# HeadsetR4.net
KiCad netlist of a schematic drawn in EAGLE
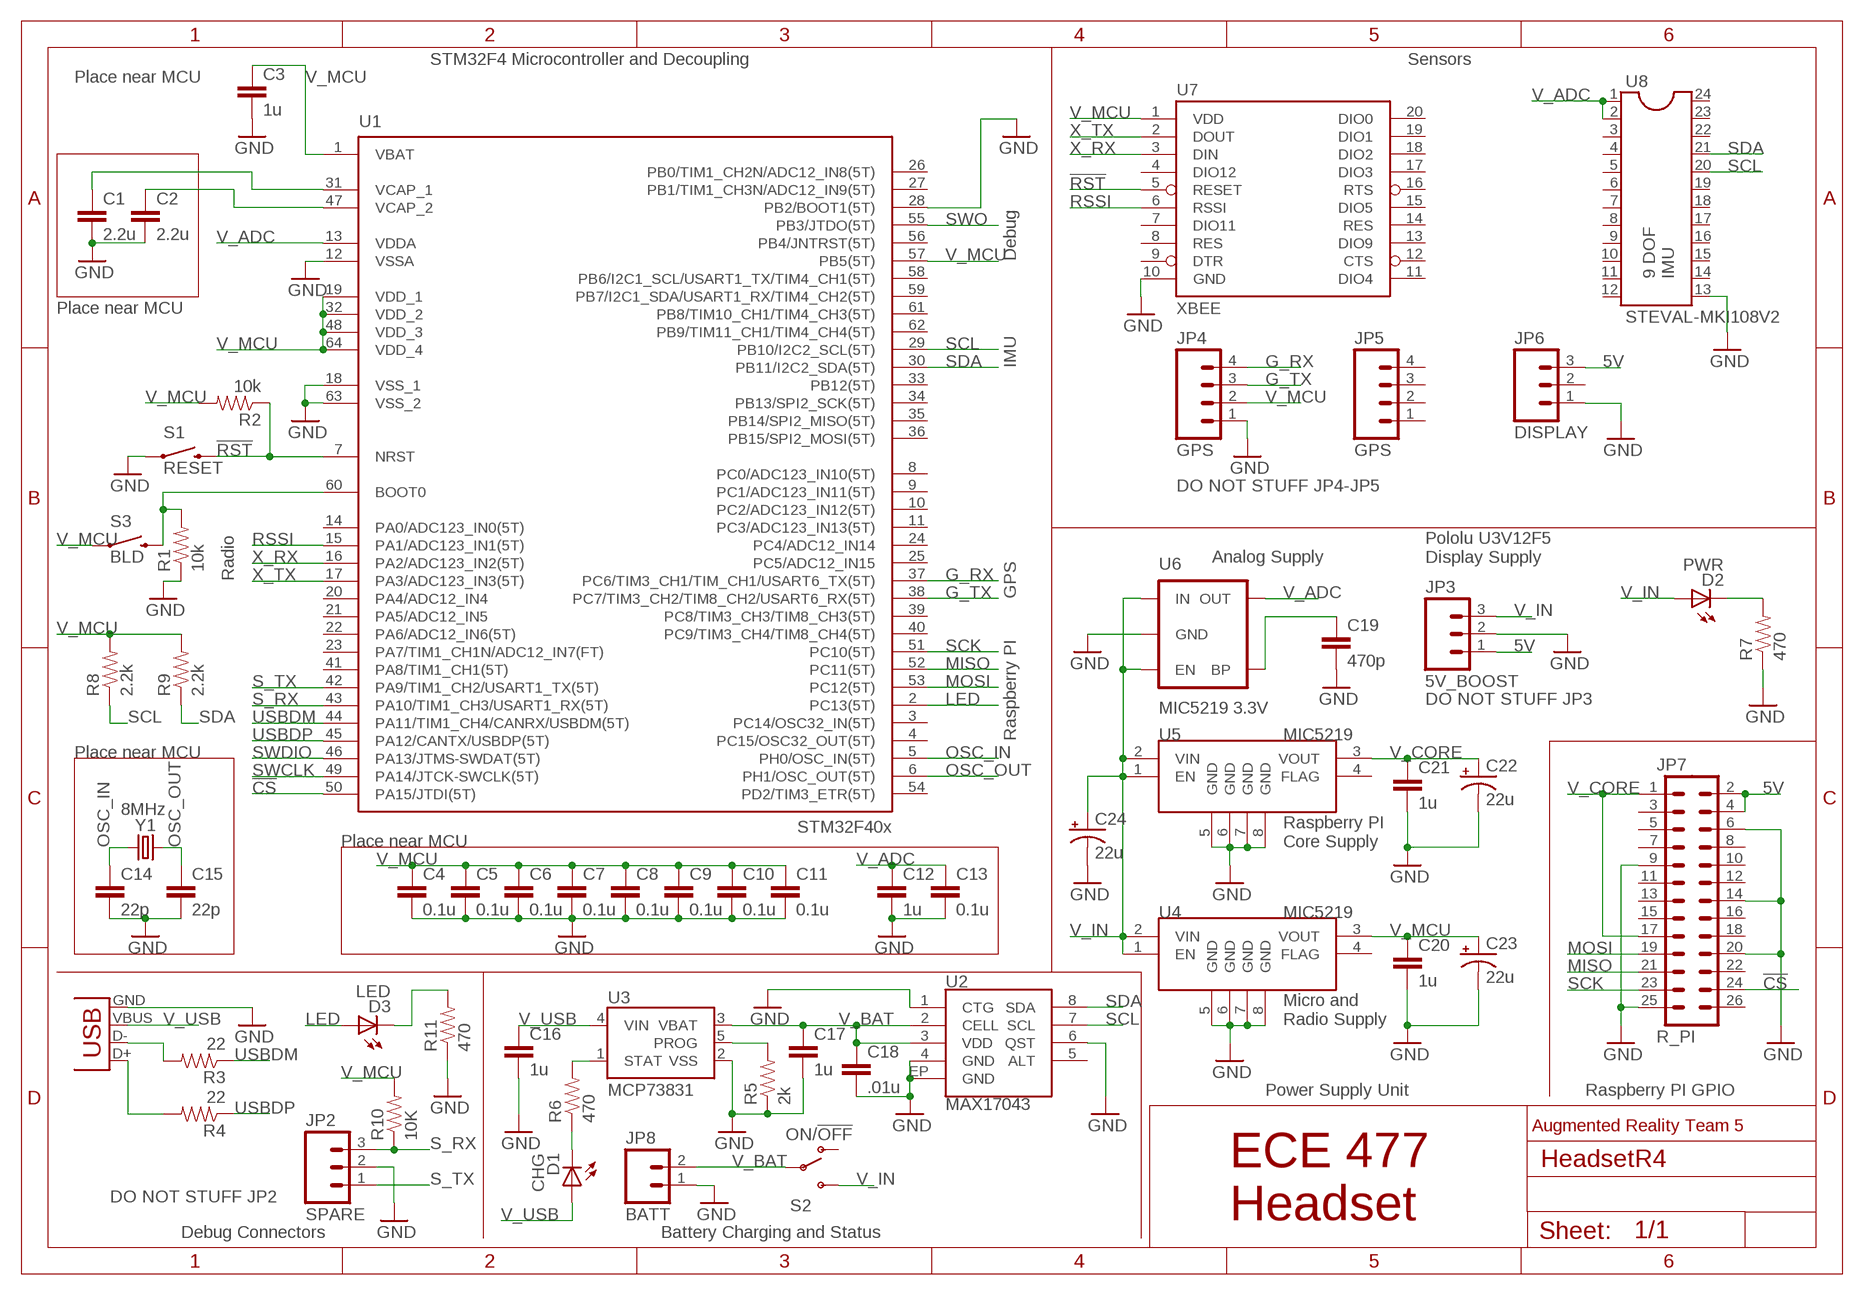
[diagram p0: schematic, sheet 1]

(export (version "E")
  (design (tool "Eeschema 10.0.6"))
  (components
    (comp (ref "C1")
      (value "2.2u")
      (footprint "eagle-import:1206")
      (libsource (lib "eagle-import") (part "CAP1206"))
    )
    (comp (ref "C2")
      (value "2.2u")
      (footprint "eagle-import:1206")
      (libsource (lib "eagle-import") (part "CAP1206"))
    )
    (comp (ref "C3")
      (value "1u")
      (footprint "eagle-import:1206")
      (libsource (lib "eagle-import") (part "CAP1206"))
    )
    (comp (ref "C4")
      (value "0.1u")
      (footprint "eagle-import:1206")
      (libsource (lib "eagle-import") (part "CAP1206"))
    )
    (comp (ref "C5")
      (value "0.1u")
      (footprint "eagle-import:1206")
      (libsource (lib "eagle-import") (part "CAP1206"))
    )
    (comp (ref "C6")
      (value "0.1u")
      (footprint "eagle-import:1206")
      (libsource (lib "eagle-import") (part "CAP1206"))
    )
    (comp (ref "C7")
      (value "0.1u")
      (footprint "eagle-import:1206")
      (libsource (lib "eagle-import") (part "CAP1206"))
    )
    (comp (ref "C8")
      (value "0.1u")
      (footprint "eagle-import:1206")
      (libsource (lib "eagle-import") (part "CAP1206"))
    )
    (comp (ref "C9")
      (value "0.1u")
      (footprint "eagle-import:1206")
      (libsource (lib "eagle-import") (part "CAP1206"))
    )
    (comp (ref "C10")
      (value "0.1u")
      (footprint "eagle-import:1206")
      (libsource (lib "eagle-import") (part "CAP1206"))
    )
    (comp (ref "C11")
      (value "0.1u")
      (footprint "eagle-import:1206")
      (libsource (lib "eagle-import") (part "CAP1206"))
    )
    (comp (ref "C12")
      (value "1u")
      (footprint "eagle-import:1206")
      (libsource (lib "eagle-import") (part "CAP1206"))
    )
    (comp (ref "C13")
      (value "0.1u")
      (footprint "eagle-import:1206")
      (libsource (lib "eagle-import") (part "CAP1206"))
    )
    (comp (ref "C14")
      (value "22p")
      (footprint "eagle-import:1206")
      (libsource (lib "eagle-import") (part "CAP1206"))
    )
    (comp (ref "C15")
      (value "22p")
      (footprint "eagle-import:1206")
      (libsource (lib "eagle-import") (part "CAP1206"))
    )
    (comp (ref "C16")
      (value "1u")
      (footprint "eagle-import:1206")
      (libsource (lib "eagle-import") (part "CAP1206"))
    )
    (comp (ref "C17")
      (value "1u")
      (footprint "eagle-import:1206")
      (libsource (lib "eagle-import") (part "CAP1206"))
    )
    (comp (ref "C18")
      (value ".01u")
      (footprint "eagle-import:1206")
      (libsource (lib "eagle-import") (part "CAP1206"))
    )
    (comp (ref "C19")
      (value "470p")
      (footprint "eagle-import:1206")
      (libsource (lib "eagle-import") (part "CAP1206"))
    )
    (comp (ref "C20")
      (value "1u")
      (footprint "eagle-import:1206")
      (libsource (lib "eagle-import") (part "CAP1206"))
    )
    (comp (ref "C21")
      (value "1u")
      (footprint "eagle-import:1206")
      (libsource (lib "eagle-import") (part "CAP1206"))
    )
    (comp (ref "C22")
      (value "22u")
      (footprint "eagle-import:PANASONIC_D")
      (libsource (lib "eagle-import") (part "CAP_POLD"))
    )
    (comp (ref "C23")
      (value "22u")
      (footprint "eagle-import:PANASONIC_D")
      (libsource (lib "eagle-import") (part "CAP_POLD"))
    )
    (comp (ref "C24")
      (value "22u")
      (footprint "eagle-import:PANASONIC_D")
      (libsource (lib "eagle-import") (part "CAP_POLD"))
    )
    (comp (ref "D1")
      (value "CHG")
      (footprint "eagle-import:LED-1206")
      (libsource (lib "eagle-import") (part "LED-RED1206"))
    )
    (comp (ref "D2")
      (value "PWR")
      (footprint "eagle-import:LED-1206")
      (libsource (lib "eagle-import") (part "LED-RED1206"))
    )
    (comp (ref "D3")
      (value "LED")
      (footprint "eagle-import:LED-1206")
      (libsource (lib "eagle-import") (part "LED-RED1206"))
    )
    (comp (ref "JP1")
      (value "USBSMD")
      (footprint "eagle-import:USB-MINIB")
      (libsource (lib "eagle-import") (part "USBSMD"))
    )
    (comp (ref "JP2")
      (value "SPARE")
      (footprint "eagle-import:1X03")
      (libsource (lib "eagle-import") (part "M03PTH"))
    )
    (comp (ref "JP3")
      (value "5V_BOOST")
      (footprint "eagle-import:1X03")
      (libsource (lib "eagle-import") (part "M03PTH"))
    )
    (comp (ref "JP4")
      (value "GPS")
      (footprint "eagle-import:1X04")
      (libsource (lib "eagle-import") (part "M04PTH"))
    )
    (comp (ref "JP5")
      (value "GPS")
      (footprint "eagle-import:1X04")
      (libsource (lib "eagle-import") (part "M04PTH"))
    )
    (comp (ref "JP6")
      (value "DISPLAY")
      (footprint "eagle-import:1X03")
      (libsource (lib "eagle-import") (part "M03PTH"))
    )
    (comp (ref "JP7")
      (value "R_PI")
      (footprint "eagle-import:2X13")
      (libsource (lib "eagle-import") (part "M13X22X13"))
    )
    (comp (ref "JP8")
      (value "BATT")
      (footprint "eagle-import:JST-2-PTH")
      (libsource (lib "eagle-import") (part "M02JST-PTH-2"))
    )
    (comp (ref "R1")
      (value "10k")
      (footprint "eagle-import:1206")
      (libsource (lib "eagle-import") (part "RES1206"))
    )
    (comp (ref "R2")
      (value "10k")
      (footprint "eagle-import:1206")
      (libsource (lib "eagle-import") (part "RES1206"))
    )
    (comp (ref "R3")
      (value "22")
      (footprint "eagle-import:1206")
      (libsource (lib "eagle-import") (part "RES1206"))
    )
    (comp (ref "R4")
      (value "22")
      (footprint "eagle-import:1206")
      (libsource (lib "eagle-import") (part "RES1206"))
    )
    (comp (ref "R5")
      (value "2k")
      (footprint "eagle-import:1206")
      (libsource (lib "eagle-import") (part "RES1206"))
    )
    (comp (ref "R6")
      (value "470")
      (footprint "eagle-import:1206")
      (libsource (lib "eagle-import") (part "RES1206"))
    )
    (comp (ref "R7")
      (value "470")
      (footprint "eagle-import:1206")
      (libsource (lib "eagle-import") (part "RES1206"))
    )
    (comp (ref "R8")
      (value "2.2k")
      (footprint "eagle-import:1206")
      (libsource (lib "eagle-import") (part "RES1206"))
    )
    (comp (ref "R9")
      (value "2.2k")
      (footprint "eagle-import:1206")
      (libsource (lib "eagle-import") (part "RES1206"))
    )
    (comp (ref "R10")
      (value "10K")
      (footprint "eagle-import:1206")
      (libsource (lib "eagle-import") (part "RES1206"))
    )
    (comp (ref "R11")
      (value "470")
      (footprint "eagle-import:1206")
      (libsource (lib "eagle-import") (part "RES1206"))
    )
    (comp (ref "S1")
      (value "RESET")
      (footprint "eagle-import:TACTILE-PTH")
      (libsource (lib "eagle-import") (part "SWITCH-MOMENTARY-2PTH"))
    )
    (comp (ref "S2")
      (value "ON/!OFF!")
      (footprint "eagle-import:SWITCH-SPDT")
      (libsource (lib "eagle-import") (part "SWITCH-SPDTPTH"))
    )
    (comp (ref "S3")
      (value "BLD")
      (footprint "eagle-import:TACTILE-PTH")
      (libsource (lib "eagle-import") (part "SWITCH-MOMENTARY-2PTH"))
    )
    (comp (ref "U1")
      (value "STM32F405RGT6")
      (footprint "eagle-import:TQFP64")
      (libsource (lib "eagle-import") (part "STM32F405R"))
    )
    (comp (ref "U2")
      (value "MAX17043")
      (footprint "eagle-import:TDFN-8")
      (libsource (lib "eagle-import") (part "MAX1704X"))
    )
    (comp (ref "U3")
      (value "MCP73831")
      (footprint "eagle-import:SOT23-5")
      (libsource (lib "eagle-import") (part "MCP73831"))
    )
    (comp (ref "U4")
      (value "MIC5219")
      (footprint "eagle-import:MSOP8")
      (libsource (lib "eagle-import") (part "V_REG_MIC5216"))
    )
    (comp (ref "U5")
      (value "MIC5219")
      (footprint "eagle-import:MSOP8")
      (libsource (lib "eagle-import") (part "V_REG_MIC5216"))
    )
    (comp (ref "U6")
      (value "MIC5219 3.3V")
      (footprint "eagle-import:SOT23-5")
      (libsource (lib "eagle-import") (part "V_REG_MIC52193.3V"))
    )
    (comp (ref "U7")
      (value "XBEE")
      (footprint "eagle-import:XBEE-1")
      (libsource (lib "eagle-import") (part "XBEE-1B1"))
    )
    (comp (ref "U8")
      (value "STEVAL-MKI108V2")
      (footprint "eagle-import:DIL24-6")
      (libsource (lib "eagle-import") (part "DIL24-6"))
    )
    (comp (ref "Y1")
      (value "8MHz")
      (footprint "eagle-import:HC49US")
      (libsource (lib "eagle-import") (part "CRYSTALHC49US"))
    )
  )
  (nets
    (net (code "1") (name "/5V") (class "Default")
      (node (ref "JP3") (pin "1") (pinfunction "1_1") (pintype "passive"))
      (node (ref "JP6") (pin "3") (pinfunction "3_3") (pintype "passive"))
      (node (ref "JP7") (pin "2") (pinfunction "2_2") (pintype "passive"))
      (node (ref "JP7") (pin "4") (pinfunction "4_4") (pintype "passive"))
    )
    (net (code "2") (name "/G_RX") (class "Default")
      (node (ref "JP4") (pin "4") (pinfunction "4_4") (pintype "passive"))
      (node (ref "U1") (pin "37") (pinfunction "PC6/TIM3_CH1/TIM_CH1/USART6_TX(5T)_37") (pintype "bidirectional"))
    )
    (net (code "3") (name "/G_TX") (class "Default")
      (node (ref "JP4") (pin "3") (pinfunction "3_3") (pintype "passive"))
      (node (ref "U1") (pin "38") (pinfunction "PC7/TIM3_CH2/TIM8_CH2/USART6_RX(5T)_38") (pintype "bidirectional"))
    )
    (net (code "4") (name "/LED") (class "Default")
      (node (ref "D3") (pin "A") (pinfunction "A_A") (pintype "passive"))
      (node (ref "U1") (pin "2") (pinfunction "PC13(5T)_2") (pintype "bidirectional"))
    )
    (net (code "5") (name "/MISO") (class "Default")
      (node (ref "JP7") (pin "21") (pinfunction "21_21") (pintype "passive"))
      (node (ref "U1") (pin "52") (pinfunction "PC11(5T)_52") (pintype "bidirectional"))
    )
    (net (code "6") (name "/MOSI") (class "Default")
      (node (ref "JP7") (pin "19") (pinfunction "19_19") (pintype "passive"))
      (node (ref "U1") (pin "53") (pinfunction "PC12(5T)_53") (pintype "bidirectional"))
    )
    (net (code "7") (name "/OSC_IN") (class "Default")
      (node (ref "C14") (pin "1") (pinfunction "1_1") (pintype "passive"))
      (node (ref "U1") (pin "5") (pinfunction "PH0/OSC_IN(5T)_5") (pintype "bidirectional"))
      (node (ref "Y1") (pin "1") (pinfunction "1_1") (pintype "passive"))
    )
    (net (code "8") (name "/OSC_OUT") (class "Default")
      (node (ref "C15") (pin "1") (pinfunction "1_1") (pintype "passive"))
      (node (ref "U1") (pin "6") (pinfunction "PH1/OSC_OUT(5T)_6") (pintype "bidirectional"))
      (node (ref "Y1") (pin "2") (pinfunction "2_2") (pintype "passive"))
    )
    (net (code "9") (name "/RSSI") (class "Default")
      (node (ref "U1") (pin "15") (pinfunction "PA1/ADC123_IN1(5T)_15") (pintype "bidirectional"))
      (node (ref "U7") (pin "6") (pinfunction "RSSI_6") (pintype "bidirectional"))
    )
    (net (code "10") (name "/SCK") (class "Default")
      (node (ref "JP7") (pin "23") (pinfunction "23_23") (pintype "passive"))
      (node (ref "U1") (pin "51") (pinfunction "PC10(5T)_51") (pintype "bidirectional"))
    )
    (net (code "11") (name "/SCL") (class "Default")
      (node (ref "R8") (pin "1") (pinfunction "1_1") (pintype "passive"))
      (node (ref "U1") (pin "29") (pinfunction "PB10/I2C2_SCL(5T)_29") (pintype "bidirectional"))
      (node (ref "U2") (pin "7") (pinfunction "SCL_7") (pintype "bidirectional"))
      (node (ref "U8") (pin "20") (pinfunction "20_20") (pintype "passive"))
    )
    (net (code "12") (name "/SDA") (class "Default")
      (node (ref "R9") (pin "1") (pinfunction "1_1") (pintype "passive"))
      (node (ref "U1") (pin "30") (pinfunction "PB11/I2C2_SDA(5T)_30") (pintype "bidirectional"))
      (node (ref "U2") (pin "8") (pinfunction "SDA_8") (pintype "bidirectional"))
      (node (ref "U8") (pin "21") (pinfunction "21_21") (pintype "passive"))
    )
    (net (code "13") (name "/SWCLK") (class "Default")
      (node (ref "U1") (pin "49") (pinfunction "PA14/JTCK-SWCLK(5T)_49") (pintype "bidirectional"))
    )
    (net (code "14") (name "/SWDIO") (class "Default")
      (node (ref "U1") (pin "46") (pinfunction "PA13/JTMS-SWDAT(5T)_46") (pintype "bidirectional"))
    )
    (net (code "15") (name "/SWO") (class "Default")
      (node (ref "U1") (pin "55") (pinfunction "PB3/JTDO(5T)_55") (pintype "bidirectional"))
    )
    (net (code "16") (name "/S_RX") (class "Default")
      (node (ref "JP2") (pin "3") (pinfunction "3_3") (pintype "passive"))
      (node (ref "R10") (pin "1") (pinfunction "1_1") (pintype "passive"))
      (node (ref "U1") (pin "43") (pinfunction "PA10/TIM1_CH3/USART1_RX(5T)_43") (pintype "bidirectional"))
    )
    (net (code "17") (name "/S_TX") (class "Default")
      (node (ref "JP2") (pin "1") (pinfunction "1_1") (pintype "passive"))
      (node (ref "U1") (pin "42") (pinfunction "PA9/TIM1_CH2/USART1_TX(5T)_42") (pintype "bidirectional"))
    )
    (net (code "18") (name "/USBDM") (class "Default")
      (node (ref "R3") (pin "1") (pinfunction "1_1") (pintype "passive"))
      (node (ref "U1") (pin "44") (pinfunction "PA11/TIM1_CH4/CANRX/USBDM(5T)_44") (pintype "bidirectional"))
    )
    (net (code "19") (name "/USBDP") (class "Default")
      (node (ref "R4") (pin "1") (pinfunction "1_1") (pintype "passive"))
      (node (ref "U1") (pin "45") (pinfunction "PA12/CANTX/USBDP(5T)_45") (pintype "bidirectional"))
    )
    (net (code "20") (name "/V_ADC") (class "Default")
      (node (ref "C12") (pin "1") (pinfunction "1_1") (pintype "passive"))
      (node (ref "C13") (pin "1") (pinfunction "1_1") (pintype "passive"))
      (node (ref "U1") (pin "13") (pinfunction "VDDA_13") (pintype "bidirectional"))
      (node (ref "U6") (pin "5") (pinfunction "OUT_5") (pintype "passive"))
      (node (ref "U8") (pin "1") (pinfunction "1_1") (pintype "passive"))
      (node (ref "U8") (pin "2") (pinfunction "2_2") (pintype "passive"))
    )
    (net (code "21") (name "/V_BAT") (class "Default")
      (node (ref "C17") (pin "1") (pinfunction "1_1") (pintype "passive"))
      (node (ref "C18") (pin "1") (pinfunction "1_1") (pintype "passive"))
      (node (ref "JP8") (pin "2") (pinfunction "2_2") (pintype "passive"))
      (node (ref "S2") (pin "2") (pinfunction "P_2") (pintype "passive"))
      (node (ref "U2") (pin "2") (pinfunction "CELL_2") (pintype "bidirectional"))
      (node (ref "U2") (pin "3") (pinfunction "VDD_3") (pintype "bidirectional"))
      (node (ref "U3") (pin "3") (pinfunction "VBAT_3") (pintype "power_in"))
    )
    (net (code "22") (name "/V_CORE") (class "Default")
      (node (ref "C21") (pin "1") (pinfunction "1_1") (pintype "passive"))
      (node (ref "C22") (pin "+") (pinfunction "+_+") (pintype "passive"))
      (node (ref "JP7") (pin "1") (pinfunction "1_1") (pintype "passive"))
      (node (ref "JP7") (pin "17") (pinfunction "17_17") (pintype "passive"))
      (node (ref "U5") (pin "3") (pinfunction "VOUT_3") (pintype "bidirectional"))
    )
    (net (code "23") (name "/V_IN") (class "Default")
      (node (ref "C24") (pin "+") (pinfunction "+_+") (pintype "passive"))
      (node (ref "D2") (pin "A") (pinfunction "A_A") (pintype "passive"))
      (node (ref "JP3") (pin "3") (pinfunction "3_3") (pintype "passive"))
      (node (ref "S2") (pin "3") (pinfunction "S_3") (pintype "passive"))
      (node (ref "U4") (pin "1") (pinfunction "EN_1") (pintype "bidirectional"))
      (node (ref "U4") (pin "2") (pinfunction "VIN_2") (pintype "bidirectional"))
      (node (ref "U5") (pin "1") (pinfunction "EN_1") (pintype "bidirectional"))
      (node (ref "U5") (pin "2") (pinfunction "VIN_2") (pintype "bidirectional"))
      (node (ref "U6") (pin "1") (pinfunction "IN_1") (pintype "input"))
      (node (ref "U6") (pin "3") (pinfunction "EN_3") (pintype "input"))
    )
    (net (code "24") (name "/V_MCU") (class "Default")
      (node (ref "C10") (pin "1") (pinfunction "1_1") (pintype "passive"))
      (node (ref "C11") (pin "1") (pinfunction "1_1") (pintype "passive"))
      (node (ref "C20") (pin "1") (pinfunction "1_1") (pintype "passive"))
      (node (ref "C23") (pin "+") (pinfunction "+_+") (pintype "passive"))
      (node (ref "C3") (pin "1") (pinfunction "1_1") (pintype "passive"))
      (node (ref "C4") (pin "1") (pinfunction "1_1") (pintype "passive"))
      (node (ref "C5") (pin "1") (pinfunction "1_1") (pintype "passive"))
      (node (ref "C6") (pin "1") (pinfunction "1_1") (pintype "passive"))
      (node (ref "C7") (pin "1") (pinfunction "1_1") (pintype "passive"))
      (node (ref "C8") (pin "1") (pinfunction "1_1") (pintype "passive"))
      (node (ref "C9") (pin "1") (pinfunction "1_1") (pintype "passive"))
      (node (ref "JP4") (pin "2") (pinfunction "2_2") (pintype "passive"))
      (node (ref "R10") (pin "2") (pinfunction "2_2") (pintype "passive"))
      (node (ref "R2") (pin "2") (pinfunction "2_2") (pintype "passive"))
      (node (ref "R8") (pin "2") (pinfunction "2_2") (pintype "passive"))
      (node (ref "R9") (pin "2") (pinfunction "2_2") (pintype "passive"))
      (node (ref "S3") (pin "1") (pinfunction "1_1") (pintype "passive"))
      (node (ref "U1") (pin "1") (pinfunction "VBAT_1") (pintype "bidirectional"))
      (node (ref "U1") (pin "19") (pinfunction "VDD_1_19") (pintype "bidirectional"))
      (node (ref "U1") (pin "32") (pinfunction "VDD_2_32") (pintype "bidirectional"))
      (node (ref "U1") (pin "48") (pinfunction "VDD_3_48") (pintype "bidirectional"))
      (node (ref "U1") (pin "57") (pinfunction "PB5(5T)_57") (pintype "bidirectional"))
      (node (ref "U1") (pin "64") (pinfunction "VDD_4_64") (pintype "bidirectional"))
      (node (ref "U4") (pin "3") (pinfunction "VOUT_3") (pintype "bidirectional"))
      (node (ref "U7") (pin "1") (pinfunction "VDD_1") (pintype "power_in"))
    )
    (net (code "25") (name "/V_USB") (class "Default")
      (node (ref "C16") (pin "1") (pinfunction "1_1") (pintype "passive"))
      (node (ref "D1") (pin "A") (pinfunction "A_A") (pintype "passive"))
      (node (ref "JP1") (pin "VBUS") (pinfunction "VBUS_VBUS") (pintype "bidirectional"))
      (node (ref "U3") (pin "4") (pinfunction "VIN_4") (pintype "power_in"))
    )
    (net (code "26") (name "/X_RX") (class "Default")
      (node (ref "U1") (pin "16") (pinfunction "PA2/ADC123_IN2(5T)_16") (pintype "bidirectional"))
      (node (ref "U7") (pin "3") (pinfunction "DIN_3") (pintype "input"))
    )
    (net (code "27") (name "/X_TX") (class "Default")
      (node (ref "U1") (pin "17") (pinfunction "PA3/ADC123_IN3(5T)_17") (pintype "bidirectional"))
      (node (ref "U7") (pin "2") (pinfunction "DOUT_2") (pintype "output"))
    )
    (net (code "28") (name "/~{CS}") (class "Default")
      (node (ref "JP7") (pin "24") (pinfunction "24_24") (pintype "passive"))
      (node (ref "U1") (pin "50") (pinfunction "PA15/JTDI(5T)_50") (pintype "bidirectional"))
    )
    (net (code "29") (name "/~{RST}") (class "Default")
      (node (ref "R2") (pin "1") (pinfunction "1_1") (pintype "passive"))
      (node (ref "S1") (pin "3") (pinfunction "2_3") (pintype "passive"))
      (node (ref "U1") (pin "7") (pinfunction "NRST_7") (pintype "bidirectional"))
      (node (ref "U7") (pin "5") (pinfunction "RESET_5") (pintype "input"))
    )
    (net (code "30") (name "GND") (class "Default")
      (node (ref "C1") (pin "2") (pinfunction "2_2") (pintype "passive"))
      (node (ref "C10") (pin "2") (pinfunction "2_2") (pintype "passive"))
      (node (ref "C11") (pin "2") (pinfunction "2_2") (pintype "passive"))
      (node (ref "C12") (pin "2") (pinfunction "2_2") (pintype "passive"))
      (node (ref "C13") (pin "2") (pinfunction "2_2") (pintype "passive"))
      (node (ref "C14") (pin "2") (pinfunction "2_2") (pintype "passive"))
      (node (ref "C15") (pin "2") (pinfunction "2_2") (pintype "passive"))
      (node (ref "C16") (pin "2") (pinfunction "2_2") (pintype "passive"))
      (node (ref "C17") (pin "2") (pinfunction "2_2") (pintype "passive"))
      (node (ref "C18") (pin "2") (pinfunction "2_2") (pintype "passive"))
      (node (ref "C19") (pin "2") (pinfunction "2_2") (pintype "passive"))
      (node (ref "C2") (pin "2") (pinfunction "2_2") (pintype "passive"))
      (node (ref "C20") (pin "2") (pinfunction "2_2") (pintype "passive"))
      (node (ref "C21") (pin "2") (pinfunction "2_2") (pintype "passive"))
      (node (ref "C22") (pin "-") (pinfunction "-_-") (pintype "passive"))
      (node (ref "C23") (pin "-") (pinfunction "-_-") (pintype "passive"))
      (node (ref "C24") (pin "-") (pinfunction "-_-") (pintype "passive"))
      (node (ref "C3") (pin "2") (pinfunction "2_2") (pintype "passive"))
      (node (ref "C4") (pin "2") (pinfunction "2_2") (pintype "passive"))
      (node (ref "C5") (pin "2") (pinfunction "2_2") (pintype "passive"))
      (node (ref "C6") (pin "2") (pinfunction "2_2") (pintype "passive"))
      (node (ref "C7") (pin "2") (pinfunction "2_2") (pintype "passive"))
      (node (ref "C8") (pin "2") (pinfunction "2_2") (pintype "passive"))
      (node (ref "C9") (pin "2") (pinfunction "2_2") (pintype "passive"))
      (node (ref "JP1") (pin "GND") (pinfunction "GND_GND") (pintype "bidirectional"))
      (node (ref "JP2") (pin "2") (pinfunction "2_2") (pintype "passive"))
      (node (ref "JP3") (pin "2") (pinfunction "2_2") (pintype "passive"))
      (node (ref "JP4") (pin "1") (pinfunction "1_1") (pintype "passive"))
      (node (ref "JP6") (pin "1") (pinfunction "1_1") (pintype "passive"))
      (node (ref "JP7") (pin "14") (pinfunction "14_14") (pintype "passive"))
      (node (ref "JP7") (pin "20") (pinfunction "20_20") (pintype "passive"))
      (node (ref "JP7") (pin "25") (pinfunction "25_25") (pintype "passive"))
      (node (ref "JP7") (pin "6") (pinfunction "6_6") (pintype "passive"))
      (node (ref "JP7") (pin "9") (pinfunction "9_9") (pintype "passive"))
      (node (ref "JP8") (pin "1") (pinfunction "1_1") (pintype "passive"))
      (node (ref "R1") (pin "1") (pinfunction "1_1") (pintype "passive"))
      (node (ref "R11") (pin "1") (pinfunction "1_1") (pintype "passive"))
      (node (ref "R5") (pin "1") (pinfunction "1_1") (pintype "passive"))
      (node (ref "R7") (pin "1") (pinfunction "1_1") (pintype "passive"))
      (node (ref "S1") (pin "1") (pinfunction "1_1") (pintype "passive"))
      (node (ref "U1") (pin "12") (pinfunction "VSSA_12") (pintype "bidirectional"))
      (node (ref "U1") (pin "18") (pinfunction "VSS_1_18") (pintype "bidirectional"))
      (node (ref "U1") (pin "28") (pinfunction "PB2/BOOT1(5T)_28") (pintype "bidirectional"))
      (node (ref "U1") (pin "63") (pinfunction "VSS_2_63") (pintype "bidirectional"))
      (node (ref "U2") (pin "1") (pinfunction "CTG_1") (pintype "bidirectional"))
      (node (ref "U2") (pin "4") (pinfunction "GND_4") (pintype "bidirectional"))
      (node (ref "U2") (pin "6") (pinfunction "QST_6") (pintype "bidirectional"))
      (node (ref "U2") (pin "EP") (pinfunction "GND_EP") (pintype "bidirectional"))
      (node (ref "U3") (pin "2") (pinfunction "VSS_2") (pintype "power_in"))
      (node (ref "U4") (pin "5") (pinfunction "GND_5") (pintype "bidirectional"))
      (node (ref "U4") (pin "6") (pinfunction "GND_6") (pintype "bidirectional"))
      (node (ref "U4") (pin "7") (pinfunction "GND_7") (pintype "bidirectional"))
      (node (ref "U4") (pin "8") (pinfunction "GND_8") (pintype "bidirectional"))
      (node (ref "U5") (pin "5") (pinfunction "GND_5") (pintype "bidirectional"))
      (node (ref "U5") (pin "6") (pinfunction "GND_6") (pintype "bidirectional"))
      (node (ref "U5") (pin "7") (pinfunction "GND_7") (pintype "bidirectional"))
      (node (ref "U5") (pin "8") (pinfunction "GND_8") (pintype "bidirectional"))
      (node (ref "U6") (pin "2") (pinfunction "GND_2") (pintype "input"))
      (node (ref "U7") (pin "10") (pinfunction "GND_10") (pintype "power_in"))
      (node (ref "U8") (pin "13") (pinfunction "13_13") (pintype "passive"))
    )
    (net (code "31") (name "Net-(D1-PadC)") (class "Default")
      (node (ref "D1") (pin "C") (pinfunction "C_C") (pintype "passive"))
      (node (ref "R6") (pin "1") (pinfunction "1_1") (pintype "passive"))
    )
    (net (code "32") (name "Net-(D2-PadC)") (class "Default")
      (node (ref "D2") (pin "C") (pinfunction "C_C") (pintype "passive"))
      (node (ref "R7") (pin "2") (pinfunction "2_2") (pintype "passive"))
    )
    (net (code "33") (name "Net-(D3-PadC)") (class "Default")
      (node (ref "D3") (pin "C") (pinfunction "C_C") (pintype "passive"))
      (node (ref "R11") (pin "2") (pinfunction "2_2") (pintype "passive"))
    )
    (net (code "34") (name "Net-(JP1-PadD+)") (class "Default")
      (node (ref "JP1") (pin "D+") (pinfunction "D+_D+") (pintype "bidirectional"))
      (node (ref "R4") (pin "2") (pinfunction "2_2") (pintype "passive"))
    )
    (net (code "35") (name "Net-(JP1-PadD-)") (class "Default")
      (node (ref "JP1") (pin "D-") (pinfunction "D-_D-") (pintype "bidirectional"))
      (node (ref "R3") (pin "2") (pinfunction "2_2") (pintype "passive"))
    )
    (net (code "36") (name "Net-(S3-2)") (class "Default")
      (node (ref "R1") (pin "2") (pinfunction "2_2") (pintype "passive"))
      (node (ref "S3") (pin "3") (pinfunction "2_3") (pintype "passive"))
      (node (ref "U1") (pin "60") (pinfunction "BOOT0_60") (pintype "bidirectional"))
    )
    (net (code "37") (name "Net-(U1-VCAP_1)") (class "Default")
      (node (ref "C1") (pin "1") (pinfunction "1_1") (pintype "passive"))
      (node (ref "U1") (pin "31") (pinfunction "VCAP_1_31") (pintype "bidirectional"))
    )
    (net (code "38") (name "Net-(U1-VCAP_2)") (class "Default")
      (node (ref "C2") (pin "1") (pinfunction "1_1") (pintype "passive"))
      (node (ref "U1") (pin "47") (pinfunction "VCAP_2_47") (pintype "bidirectional"))
    )
    (net (code "39") (name "Net-(U3-PROG)") (class "Default")
      (node (ref "R5") (pin "2") (pinfunction "2_2") (pintype "passive"))
      (node (ref "U3") (pin "5") (pinfunction "PROG_5") (pintype "input"))
    )
    (net (code "40") (name "Net-(U3-STAT)") (class "Default")
      (node (ref "R6") (pin "2") (pinfunction "2_2") (pintype "passive"))
      (node (ref "U3") (pin "1") (pinfunction "STAT_1") (pintype "output"))
    )
    (net (code "41") (name "Net-(U6-BP)") (class "Default")
      (node (ref "C19") (pin "1") (pinfunction "1_1") (pintype "passive"))
      (node (ref "U6") (pin "4") (pinfunction "BP_4") (pintype "input"))
    )
    (net (code "42") (name "unconnected-(JP5-Pad1)") (class "Default")
      (node (ref "JP5") (pin "1") (pinfunction "1_1") (pintype "passive"))
    )
    (net (code "43") (name "unconnected-(JP5-Pad2)") (class "Default")
      (node (ref "JP5") (pin "2") (pinfunction "2_2") (pintype "passive"))
    )
    (net (code "44") (name "unconnected-(JP5-Pad3)") (class "Default")
      (node (ref "JP5") (pin "3") (pinfunction "3_3") (pintype "passive"))
    )
    (net (code "45") (name "unconnected-(JP5-Pad4)") (class "Default")
      (node (ref "JP5") (pin "4") (pinfunction "4_4") (pintype "passive"))
    )
    (net (code "46") (name "unconnected-(JP6-Pad2)") (class "Default")
      (node (ref "JP6") (pin "2") (pinfunction "2_2") (pintype "passive"))
    )
    (net (code "47") (name "unconnected-(JP7-Pad3)") (class "Default")
      (node (ref "JP7") (pin "3") (pinfunction "3_3") (pintype "passive"))
    )
    (net (code "48") (name "unconnected-(JP7-Pad5)") (class "Default")
      (node (ref "JP7") (pin "5") (pinfunction "5_5") (pintype "passive"))
    )
    (net (code "49") (name "unconnected-(JP7-Pad7)") (class "Default")
      (node (ref "JP7") (pin "7") (pinfunction "7_7") (pintype "passive"))
    )
    (net (code "50") (name "unconnected-(JP7-Pad8)") (class "Default")
      (node (ref "JP7") (pin "8") (pinfunction "8_8") (pintype "passive"))
    )
    (net (code "51") (name "unconnected-(JP7-Pad10)") (class "Default")
      (node (ref "JP7") (pin "10") (pinfunction "10_10") (pintype "passive"))
    )
    (net (code "52") (name "unconnected-(JP7-Pad11)") (class "Default")
      (node (ref "JP7") (pin "11") (pinfunction "11_11") (pintype "passive"))
    )
    (net (code "53") (name "unconnected-(JP7-Pad12)") (class "Default")
      (node (ref "JP7") (pin "12") (pinfunction "12_12") (pintype "passive"))
    )
    (net (code "54") (name "unconnected-(JP7-Pad13)") (class "Default")
      (node (ref "JP7") (pin "13") (pinfunction "13_13") (pintype "passive"))
    )
    (net (code "55") (name "unconnected-(JP7-Pad15)") (class "Default")
      (node (ref "JP7") (pin "15") (pinfunction "15_15") (pintype "passive"))
    )
    (net (code "56") (name "unconnected-(JP7-Pad16)") (class "Default")
      (node (ref "JP7") (pin "16") (pinfunction "16_16") (pintype "passive"))
    )
    (net (code "57") (name "unconnected-(JP7-Pad18)") (class "Default")
      (node (ref "JP7") (pin "18") (pinfunction "18_18") (pintype "passive"))
    )
    (net (code "58") (name "unconnected-(JP7-Pad22)") (class "Default")
      (node (ref "JP7") (pin "22") (pinfunction "22_22") (pintype "passive"))
    )
    (net (code "59") (name "unconnected-(JP7-Pad26)") (class "Default")
      (node (ref "JP7") (pin "26") (pinfunction "26_26") (pintype "passive"))
    )
    (net (code "60") (name "unconnected-(S2-O-Pad1)") (class "Default")
      (node (ref "S2") (pin "1") (pinfunction "O_1") (pintype "passive"))
    )
    (net (code "61") (name "unconnected-(U1-PA0{slash}ADC123_IN0(5T)-Pad14)") (class "Default")
      (node (ref "U1") (pin "14") (pinfunction "PA0/ADC123_IN0(5T)_14") (pintype "bidirectional"))
    )
    (net (code "62") (name "unconnected-(U1-PA4{slash}ADC12_IN4-Pad20)") (class "Default")
      (node (ref "U1") (pin "20") (pinfunction "PA4/ADC12_IN4_20") (pintype "bidirectional"))
    )
    (net (code "63") (name "unconnected-(U1-PA5{slash}ADC12_IN5-Pad21)") (class "Default")
      (node (ref "U1") (pin "21") (pinfunction "PA5/ADC12_IN5_21") (pintype "bidirectional"))
    )
    (net (code "64") (name "unconnected-(U1-PA6{slash}ADC12_IN6(5T)-Pad22)") (class "Default")
      (node (ref "U1") (pin "22") (pinfunction "PA6/ADC12_IN6(5T)_22") (pintype "bidirectional"))
    )
    (net (code "65") (name "unconnected-(U1-PA7{slash}TIM1_CH1N{slash}ADC12_IN7(FT)-Pad23)") (class "Default")
      (node (ref "U1") (pin "23") (pinfunction "PA7/TIM1_CH1N/ADC12_IN7(FT)_23") (pintype "bidirectional"))
    )
    (net (code "66") (name "unconnected-(U1-PA8{slash}TIM1_CH1(5T)-Pad41)") (class "Default")
      (node (ref "U1") (pin "41") (pinfunction "PA8/TIM1_CH1(5T)_41") (pintype "bidirectional"))
    )
    (net (code "67") (name "unconnected-(U1-PB0{slash}TIM1_CH2N{slash}ADC12_IN8(5T)-Pad26)") (class "Default")
      (node (ref "U1") (pin "26") (pinfunction "PB0/TIM1_CH2N/ADC12_IN8(5T)_26") (pintype "bidirectional"))
    )
    (net (code "68") (name "unconnected-(U1-PB1{slash}TIM1_CH3N{slash}ADC12_IN9(5T)-Pad27)") (class "Default")
      (node (ref "U1") (pin "27") (pinfunction "PB1/TIM1_CH3N/ADC12_IN9(5T)_27") (pintype "bidirectional"))
    )
    (net (code "69") (name "unconnected-(U1-PB4{slash}JNTRST(5T)-Pad56)") (class "Default")
      (node (ref "U1") (pin "56") (pinfunction "PB4/JNTRST(5T)_56") (pintype "bidirectional"))
    )
    (net (code "70") (name "unconnected-(U1-PB6{slash}I2C1_SCL{slash}USART1_TX{slash}TIM4_CH1(5T)-Pad58)") (class "Default")
      (node (ref "U1") (pin "58") (pinfunction "PB6/I2C1_SCL/USART1_TX/TIM4_CH1(5T)_58") (pintype "bidirectional"))
    )
    (net (code "71") (name "unconnected-(U1-PB7{slash}I2C1_SDA{slash}USART1_RX{slash}TIM4_CH2(5T)-Pad59)") (class "Default")
      (node (ref "U1") (pin "59") (pinfunction "PB7/I2C1_SDA/USART1_RX/TIM4_CH2(5T)_59") (pintype "bidirectional"))
    )
    (net (code "72") (name "unconnected-(U1-PB8{slash}TIM10_CH1{slash}TIM4_CH3(5T)-Pad61)") (class "Default")
      (node (ref "U1") (pin "61") (pinfunction "PB8/TIM10_CH1/TIM4_CH3(5T)_61") (pintype "bidirectional"))
    )
    (net (code "73") (name "unconnected-(U1-PB9{slash}TIM11_CH1{slash}TIM4_CH4(5T)-Pad62)") (class "Default")
      (node (ref "U1") (pin "62") (pinfunction "PB9/TIM11_CH1/TIM4_CH4(5T)_62") (pintype "bidirectional"))
    )
    (net (code "74") (name "unconnected-(U1-PB12(5T)-Pad33)") (class "Default")
      (node (ref "U1") (pin "33") (pinfunction "PB12(5T)_33") (pintype "bidirectional"))
    )
    (net (code "75") (name "unconnected-(U1-PB13{slash}SPI2_SCK(5T)-Pad34)") (class "Default")
      (node (ref "U1") (pin "34") (pinfunction "PB13/SPI2_SCK(5T)_34") (pintype "bidirectional"))
    )
    (net (code "76") (name "unconnected-(U1-PB14{slash}SPI2_MISO(5T)-Pad35)") (class "Default")
      (node (ref "U1") (pin "35") (pinfunction "PB14/SPI2_MISO(5T)_35") (pintype "bidirectional"))
    )
    (net (code "77") (name "unconnected-(U1-PB15{slash}SPI2_MOSI(5T)-Pad36)") (class "Default")
      (node (ref "U1") (pin "36") (pinfunction "PB15/SPI2_MOSI(5T)_36") (pintype "bidirectional"))
    )
    (net (code "78") (name "unconnected-(U1-PC0{slash}ADC123_IN10(5T)-Pad8)") (class "Default")
      (node (ref "U1") (pin "8") (pinfunction "PC0/ADC123_IN10(5T)_8") (pintype "bidirectional"))
    )
    (net (code "79") (name "unconnected-(U1-PC1{slash}ADC123_IN11(5T)-Pad9)") (class "Default")
      (node (ref "U1") (pin "9") (pinfunction "PC1/ADC123_IN11(5T)_9") (pintype "bidirectional"))
    )
    (net (code "80") (name "unconnected-(U1-PC2{slash}ADC123_IN12(5T)-Pad10)") (class "Default")
      (node (ref "U1") (pin "10") (pinfunction "PC2/ADC123_IN12(5T)_10") (pintype "bidirectional"))
    )
    (net (code "81") (name "unconnected-(U1-PC3{slash}ADC123_IN13(5T)-Pad11)") (class "Default")
      (node (ref "U1") (pin "11") (pinfunction "PC3/ADC123_IN13(5T)_11") (pintype "bidirectional"))
    )
    (net (code "82") (name "unconnected-(U1-PC4{slash}ADC12_IN14-Pad24)") (class "Default")
      (node (ref "U1") (pin "24") (pinfunction "PC4/ADC12_IN14_24") (pintype "bidirectional"))
    )
    (net (code "83") (name "unconnected-(U1-PC5{slash}ADC12_IN15-Pad25)") (class "Default")
      (node (ref "U1") (pin "25") (pinfunction "PC5/ADC12_IN15_25") (pintype "bidirectional"))
    )
    (net (code "84") (name "unconnected-(U1-PC8{slash}TIM3_CH3{slash}TIM8_CH3(5T)-Pad39)") (class "Default")
      (node (ref "U1") (pin "39") (pinfunction "PC8/TIM3_CH3/TIM8_CH3(5T)_39") (pintype "bidirectional"))
    )
    (net (code "85") (name "unconnected-(U1-PC9{slash}TIM3_CH4{slash}TIM8_CH4(5T)-Pad40)") (class "Default")
      (node (ref "U1") (pin "40") (pinfunction "PC9/TIM3_CH4/TIM8_CH4(5T)_40") (pintype "bidirectional"))
    )
    (net (code "86") (name "unconnected-(U1-PC14{slash}OSC32_IN(5T)-Pad3)") (class "Default")
      (node (ref "U1") (pin "3") (pinfunction "PC14/OSC32_IN(5T)_3") (pintype "bidirectional"))
    )
    (net (code "87") (name "unconnected-(U1-PC15{slash}OSC32_OUT(5T)-Pad4)") (class "Default")
      (node (ref "U1") (pin "4") (pinfunction "PC15/OSC32_OUT(5T)_4") (pintype "bidirectional"))
    )
    (net (code "88") (name "unconnected-(U1-PD2{slash}TIM3_ETR(5T)-Pad54)") (class "Default")
      (node (ref "U1") (pin "54") (pinfunction "PD2/TIM3_ETR(5T)_54") (pintype "bidirectional"))
    )
    (net (code "89") (name "unconnected-(U2-ALT-Pad5)") (class "Default")
      (node (ref "U2") (pin "5") (pinfunction "ALT_5") (pintype "bidirectional"))
    )
    (net (code "90") (name "unconnected-(U4-FLAG-Pad4)") (class "Default")
      (node (ref "U4") (pin "4") (pinfunction "FLAG_4") (pintype "bidirectional"))
    )
    (net (code "91") (name "unconnected-(U5-FLAG-Pad4)") (class "Default")
      (node (ref "U5") (pin "4") (pinfunction "FLAG_4") (pintype "bidirectional"))
    )
    (net (code "92") (name "unconnected-(U7-CTS-Pad12)") (class "Default")
      (node (ref "U7") (pin "12") (pinfunction "CTS_12") (pintype "output"))
    )
    (net (code "93") (name "unconnected-(U7-DIO0-Pad20)") (class "Default")
      (node (ref "U7") (pin "20") (pinfunction "DIO0_20") (pintype "bidirectional"))
    )
    (net (code "94") (name "unconnected-(U7-DIO1-Pad19)") (class "Default")
      (node (ref "U7") (pin "19") (pinfunction "DIO1_19") (pintype "bidirectional"))
    )
    (net (code "95") (name "unconnected-(U7-DIO2-Pad18)") (class "Default")
      (node (ref "U7") (pin "18") (pinfunction "DIO2_18") (pintype "bidirectional"))
    )
    (net (code "96") (name "unconnected-(U7-DIO3-Pad17)") (class "Default")
      (node (ref "U7") (pin "17") (pinfunction "DIO3_17") (pintype "bidirectional"))
    )
    (net (code "97") (name "unconnected-(U7-DIO4-Pad11)") (class "Default")
      (node (ref "U7") (pin "11") (pinfunction "DIO4_11") (pintype "bidirectional"))
    )
    (net (code "98") (name "unconnected-(U7-DIO5-Pad15)") (class "Default")
      (node (ref "U7") (pin "15") (pinfunction "DIO5_15") (pintype "bidirectional"))
    )
    (net (code "99") (name "unconnected-(U7-DIO9-Pad13)") (class "Default")
      (node (ref "U7") (pin "13") (pinfunction "DIO9_13") (pintype "bidirectional"))
    )
    (net (code "100") (name "unconnected-(U7-DIO11-Pad7)") (class "Default")
      (node (ref "U7") (pin "7") (pinfunction "DIO11_7") (pintype "bidirectional"))
    )
    (net (code "101") (name "unconnected-(U7-DIO12-Pad4)") (class "Default")
      (node (ref "U7") (pin "4") (pinfunction "DIO12_4") (pintype "bidirectional"))
    )
    (net (code "102") (name "unconnected-(U7-DTR-Pad9)") (class "Default")
      (node (ref "U7") (pin "9") (pinfunction "DTR_9") (pintype "bidirectional"))
    )
    (net (code "103") (name "unconnected-(U7-RES-Pad8)") (class "Default")
      (node (ref "U7") (pin "8") (pinfunction "RES_8") (pintype "bidirectional"))
    )
    (net (code "104") (name "unconnected-(U7-RES-Pad14)") (class "Default")
      (node (ref "U7") (pin "14") (pinfunction "RES_14") (pintype "bidirectional"))
    )
    (net (code "105") (name "unconnected-(U7-RTS-Pad16)") (class "Default")
      (node (ref "U7") (pin "16") (pinfunction "RTS_16") (pintype "input"))
    )
    (net (code "106") (name "unconnected-(U8-Pad3)") (class "Default")
      (node (ref "U8") (pin "3") (pinfunction "3_3") (pintype "passive"))
    )
    (net (code "107") (name "unconnected-(U8-Pad4)") (class "Default")
      (node (ref "U8") (pin "4") (pinfunction "4_4") (pintype "passive"))
    )
    (net (code "108") (name "unconnected-(U8-Pad5)") (class "Default")
      (node (ref "U8") (pin "5") (pinfunction "5_5") (pintype "passive"))
    )
    (net (code "109") (name "unconnected-(U8-Pad6)") (class "Default")
      (node (ref "U8") (pin "6") (pinfunction "6_6") (pintype "passive"))
    )
    (net (code "110") (name "unconnected-(U8-Pad7)") (class "Default")
      (node (ref "U8") (pin "7") (pinfunction "7_7") (pintype "passive"))
    )
    (net (code "111") (name "unconnected-(U8-Pad8)") (class "Default")
      (node (ref "U8") (pin "8") (pinfunction "8_8") (pintype "passive"))
    )
    (net (code "112") (name "unconnected-(U8-Pad9)") (class "Default")
      (node (ref "U8") (pin "9") (pinfunction "9_9") (pintype "passive"))
    )
    (net (code "113") (name "unconnected-(U8-Pad10)") (class "Default")
      (node (ref "U8") (pin "10") (pinfunction "10_10") (pintype "passive"))
    )
    (net (code "114") (name "unconnected-(U8-Pad11)") (class "Default")
      (node (ref "U8") (pin "11") (pinfunction "11_11") (pintype "passive"))
    )
    (net (code "115") (name "unconnected-(U8-Pad12)") (class "Default")
      (node (ref "U8") (pin "12") (pinfunction "12_12") (pintype "passive"))
    )
    (net (code "116") (name "unconnected-(U8-Pad14)") (class "Default")
      (node (ref "U8") (pin "14") (pinfunction "14_14") (pintype "passive"))
    )
    (net (code "117") (name "unconnected-(U8-Pad15)") (class "Default")
      (node (ref "U8") (pin "15") (pinfunction "15_15") (pintype "passive"))
    )
    (net (code "118") (name "unconnected-(U8-Pad16)") (class "Default")
      (node (ref "U8") (pin "16") (pinfunction "16_16") (pintype "passive"))
    )
    (net (code "119") (name "unconnected-(U8-Pad17)") (class "Default")
      (node (ref "U8") (pin "17") (pinfunction "17_17") (pintype "passive"))
    )
    (net (code "120") (name "unconnected-(U8-Pad18)") (class "Default")
      (node (ref "U8") (pin "18") (pinfunction "18_18") (pintype "passive"))
    )
    (net (code "121") (name "unconnected-(U8-Pad19)") (class "Default")
      (node (ref "U8") (pin "19") (pinfunction "19_19") (pintype "passive"))
    )
    (net (code "122") (name "unconnected-(U8-Pad22)") (class "Default")
      (node (ref "U8") (pin "22") (pinfunction "22_22") (pintype "passive"))
    )
    (net (code "123") (name "unconnected-(U8-Pad23)") (class "Default")
      (node (ref "U8") (pin "23") (pinfunction "23_23") (pintype "passive"))
    )
    (net (code "124") (name "unconnected-(U8-Pad24)") (class "Default")
      (node (ref "U8") (pin "24") (pinfunction "24_24") (pintype "passive"))
    )
  )
)
